# oplab_pth.net
KiCad netlist of a schematic drawn in EAGLE
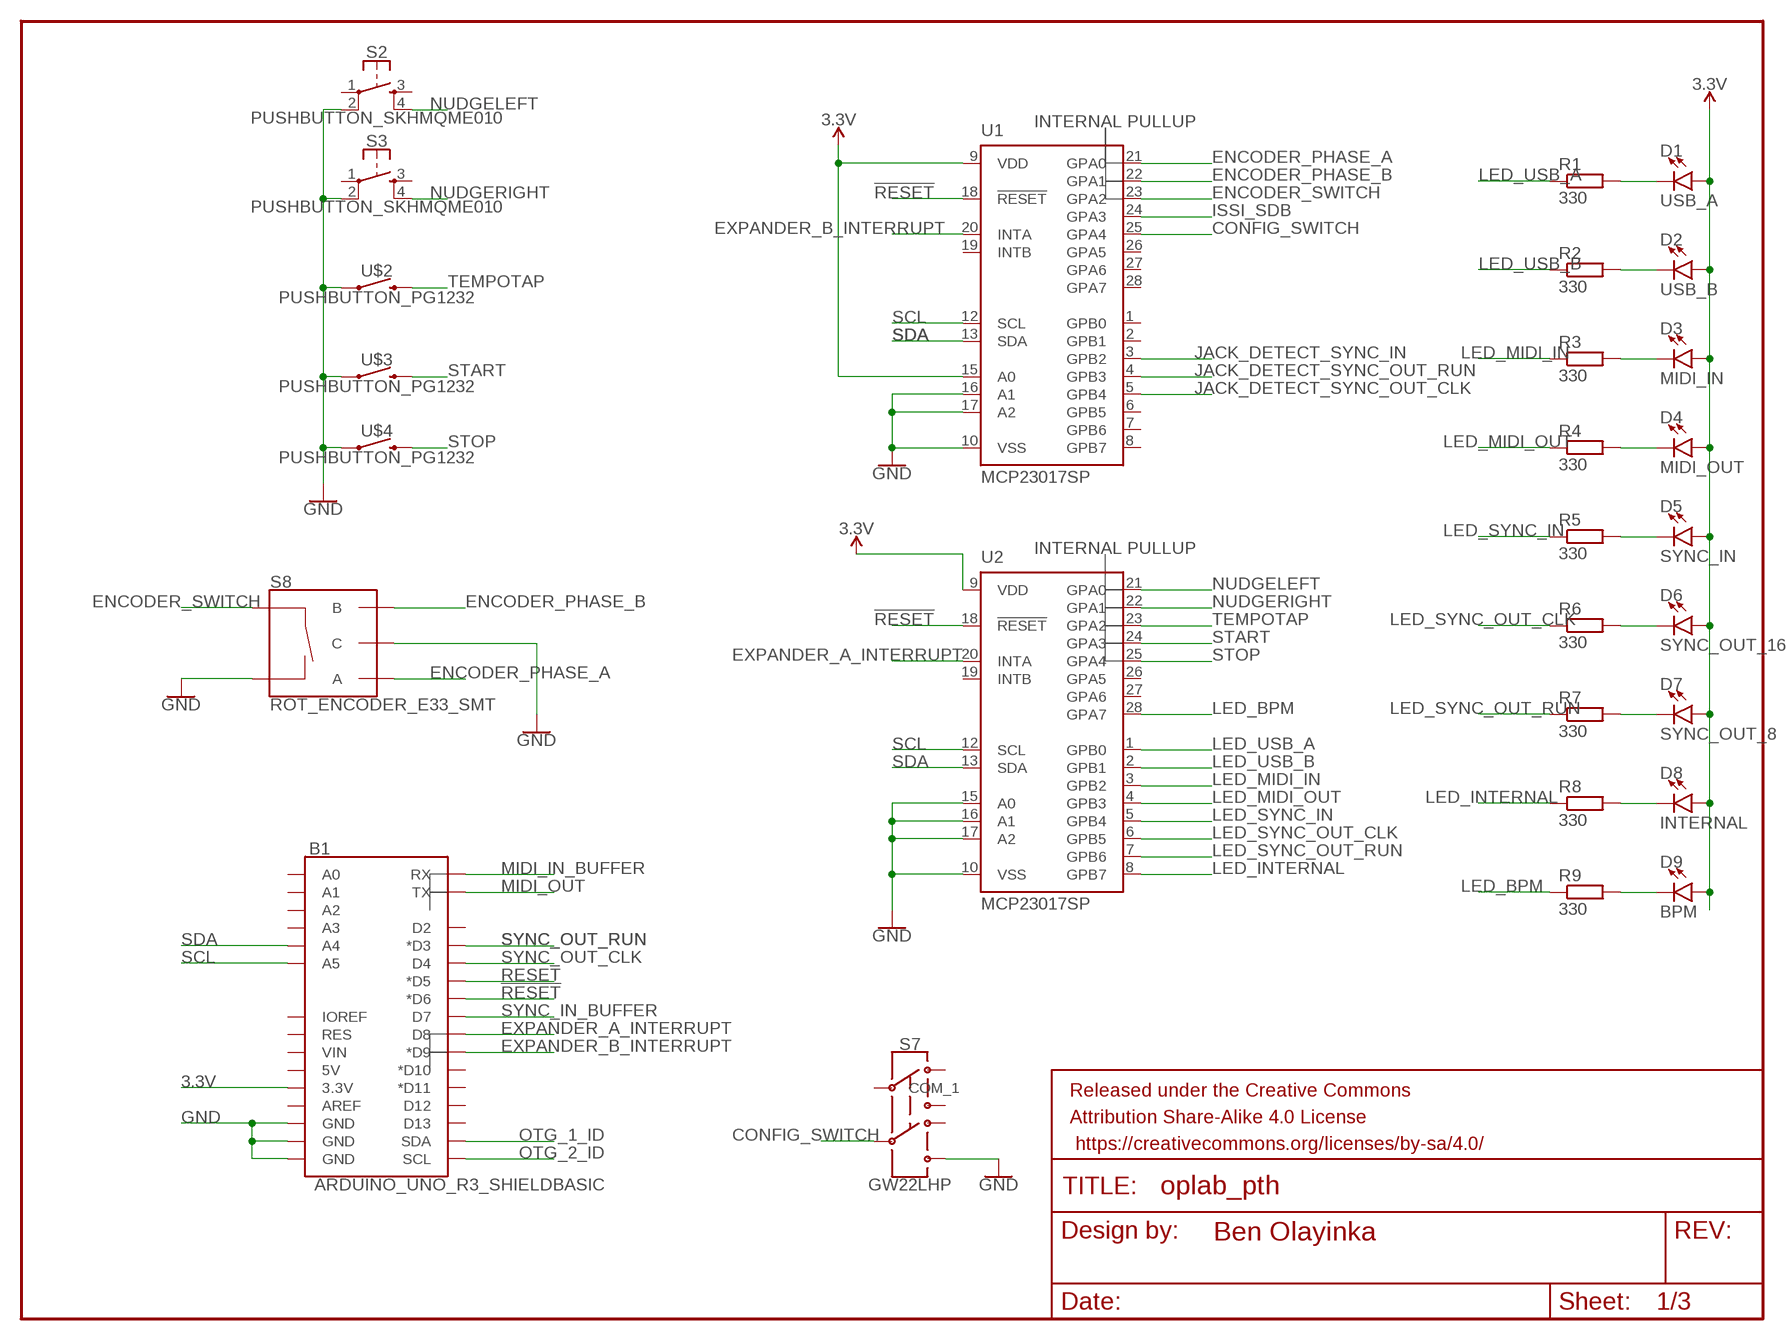
[diagram p0: schematic, sheet 1]
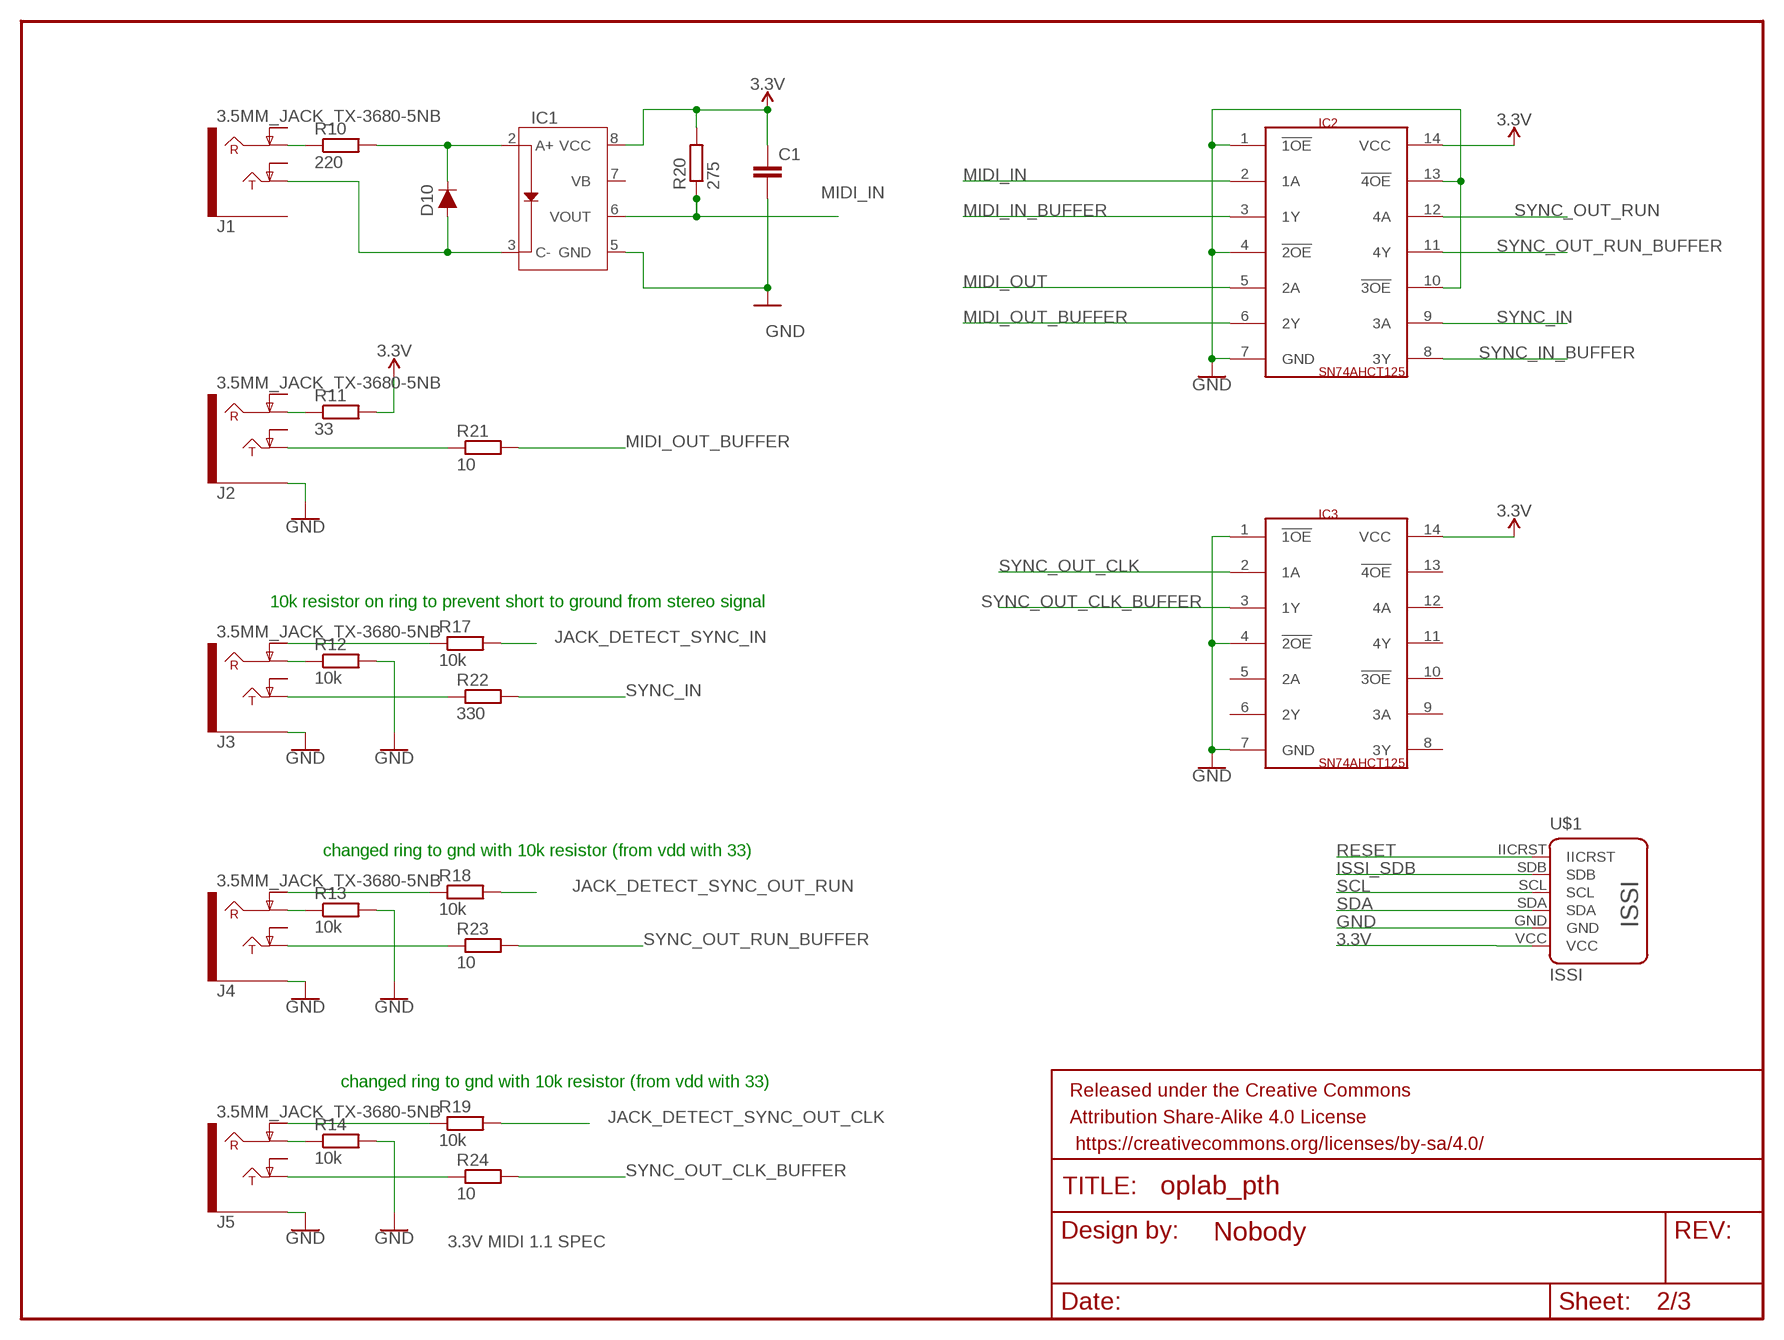
[diagram p1: schematic, sheet 2]
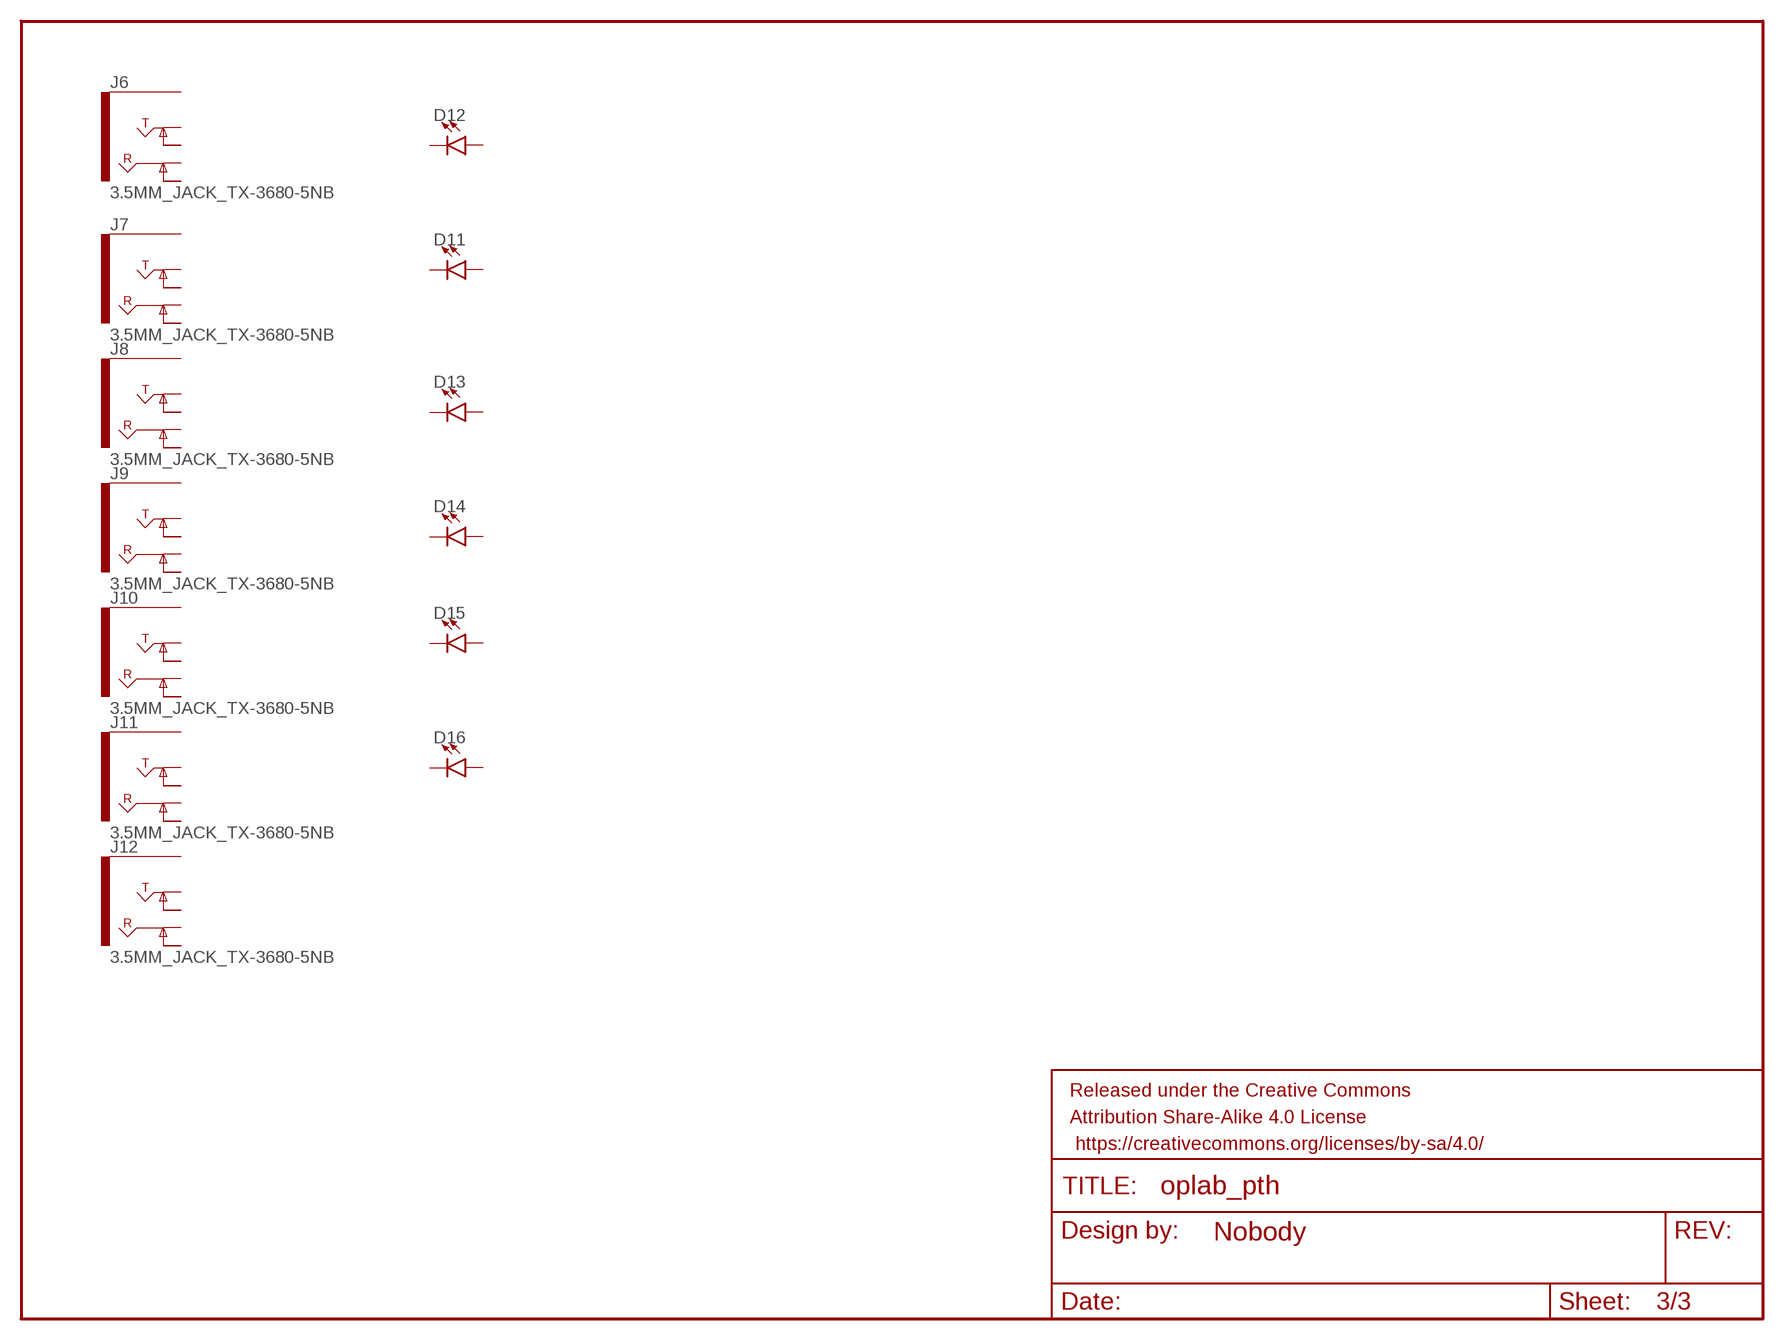
[diagram p2: schematic, sheet 3]

(export (version "E")
  (design (tool "Eeschema 10.0.6"))
  (components
    (comp (ref "C1")
      (value "C-EU025-024X044")
      (footprint "eagle-import:C025-024X044")
      (libsource (lib "eagle-import") (part "C-EU025-024X044"))
    )
    (comp (ref "D10")
      (value "200mA/100V/1V")
      (footprint "eagle-import:DIODE-1N4148")
      (libsource (lib "eagle-import") (part "DIODE-1N4148"))
    )
    (comp (ref "FRAME2")
      (value "FRAME-LETTERNO_PACKAGE")
      (footprint "eagle-import:DUMMY")
      (fields (field (name "DESIGNER") "Nobody"))
      (libsource (lib "eagle-import") (part "FRAME-LETTERNO_PACKAGE"))
    )
    (comp (ref "IC1")
      (value "OPTO_DARLINGTON_HCPL0701")
      (footprint "eagle-import:OPTO_DARLINGTON_SOIC127P594X363-8N")
      (fields
        (field (name "MANUFACTURER_PART_NUMBER") "HCPL0701")
        (field (name "MOUSER_PART_NUMBER") "512-HCPL0701")
        (field (name "RS_PART_NUMBER") "9034263P")
      )
      (libsource (lib "eagle-import") (part "OPTO_DARLINGTON_HCPL0701"))
    )
    (comp (ref "IC2")
      (value "SN74AHCT125")
      (footprint "eagle-import:SN74AHCT_DIP794W53P254L1930H508Q14N")
      (fields
        (field (name "MANUFACTURER_PART_NUMBER") "SN74HCT14N")
        (field (name "MOUSER_PART_NUMBER") "595-SN74HCT14N")
        (field (name "RS_PART_NUMBER") "0526331")
      )
      (libsource (lib "eagle-import") (part "SN74AHCT125"))
    )
    (comp (ref "IC3")
      (value "SN74AHCT125")
      (footprint "eagle-import:SN74AHCT_DIP794W53P254L1930H508Q14N")
      (fields
        (field (name "MANUFACTURER_PART_NUMBER") "SN74HCT14N")
        (field (name "MOUSER_PART_NUMBER") "595-SN74HCT14N")
        (field (name "RS_PART_NUMBER") "0526331")
      )
      (libsource (lib "eagle-import") (part "SN74AHCT125"))
    )
    (comp (ref "J1")
      (value "3.5MM_JACK_TX-3680-5NB")
      (footprint "eagle-import:3.5MM_JACK_TX36805NB")
      (libsource (lib "eagle-import") (part "3.5MM_JACK_TX-3680-5NB"))
    )
    (comp (ref "J2")
      (value "3.5MM_JACK_TX-3680-5NB")
      (footprint "eagle-import:3.5MM_JACK_TX36805NB")
      (libsource (lib "eagle-import") (part "3.5MM_JACK_TX-3680-5NB"))
    )
    (comp (ref "J3")
      (value "3.5MM_JACK_TX-3680-5NB")
      (footprint "eagle-import:3.5MM_JACK_TX36805NB")
      (libsource (lib "eagle-import") (part "3.5MM_JACK_TX-3680-5NB"))
    )
    (comp (ref "J4")
      (value "3.5MM_JACK_TX-3680-5NB")
      (footprint "eagle-import:3.5MM_JACK_TX36805NB")
      (libsource (lib "eagle-import") (part "3.5MM_JACK_TX-3680-5NB"))
    )
    (comp (ref "J5")
      (value "3.5MM_JACK_TX-3680-5NB")
      (footprint "eagle-import:3.5MM_JACK_TX36805NB")
      (libsource (lib "eagle-import") (part "3.5MM_JACK_TX-3680-5NB"))
    )
    (comp (ref "R10")
      (value "220")
      (footprint "eagle-import:0207_10")
      (libsource (lib "eagle-import") (part "R-EU_0207/10"))
    )
    (comp (ref "R11")
      (value "33")
      (footprint "eagle-import:0207_10")
      (libsource (lib "eagle-import") (part "R-EU_0207/10"))
    )
    (comp (ref "R12")
      (value "10k")
      (footprint "eagle-import:0207_10")
      (libsource (lib "eagle-import") (part "R-EU_0207/10"))
    )
    (comp (ref "R13")
      (value "10k")
      (footprint "eagle-import:0207_10")
      (libsource (lib "eagle-import") (part "R-EU_0207/10"))
    )
    (comp (ref "R14")
      (value "10k")
      (footprint "eagle-import:0207_10")
      (libsource (lib "eagle-import") (part "R-EU_0207/10"))
    )
    (comp (ref "R17")
      (value "10k")
      (footprint "eagle-import:0207_10")
      (libsource (lib "eagle-import") (part "R-EU_0207/10"))
    )
    (comp (ref "R18")
      (value "10k")
      (footprint "eagle-import:0207_10")
      (libsource (lib "eagle-import") (part "R-EU_0207/10"))
    )
    (comp (ref "R19")
      (value "10k")
      (footprint "eagle-import:0207_10")
      (libsource (lib "eagle-import") (part "R-EU_0207/10"))
    )
    (comp (ref "R20")
      (value "275")
      (footprint "eagle-import:0207_10")
      (libsource (lib "eagle-import") (part "R-EU_0207/10"))
    )
    (comp (ref "R21")
      (value "10")
      (footprint "eagle-import:0207_10")
      (libsource (lib "eagle-import") (part "R-EU_0207/10"))
    )
    (comp (ref "R22")
      (value "330")
      (footprint "eagle-import:0207_10")
      (libsource (lib "eagle-import") (part "R-EU_0207/10"))
    )
    (comp (ref "R23")
      (value "10")
      (footprint "eagle-import:0207_10")
      (libsource (lib "eagle-import") (part "R-EU_0207/10"))
    )
    (comp (ref "R24")
      (value "10")
      (footprint "eagle-import:0207_10")
      (libsource (lib "eagle-import") (part "R-EU_0207/10"))
    )
    (comp (ref "U$1")
      (value "ISSI")
      (footprint "eagle-import:ISSI")
      (libsource (lib "eagle-import") (part "ISSI"))
    )
    (comp (ref "D11")
      (value "LED5MM")
      (footprint "eagle-import:LED_5MM")
      (libsource (lib "eagle-import") (part "LED5MM"))
    )
    (comp (ref "D12")
      (value "LED5MM")
      (footprint "eagle-import:LED_5MM")
      (libsource (lib "eagle-import") (part "LED5MM"))
    )
    (comp (ref "D13")
      (value "LED5MM")
      (footprint "eagle-import:LED_5MM")
      (libsource (lib "eagle-import") (part "LED5MM"))
    )
    (comp (ref "D14")
      (value "LED5MM")
      (footprint "eagle-import:LED_5MM")
      (libsource (lib "eagle-import") (part "LED5MM"))
    )
    (comp (ref "D15")
      (value "LED5MM")
      (footprint "eagle-import:LED_5MM")
      (libsource (lib "eagle-import") (part "LED5MM"))
    )
    (comp (ref "D16")
      (value "LED5MM")
      (footprint "eagle-import:LED_5MM")
      (libsource (lib "eagle-import") (part "LED5MM"))
    )
    (comp (ref "FRAME3")
      (value "FRAME-LETTERNO_PACKAGE")
      (footprint "eagle-import:DUMMY")
      (fields (field (name "DESIGNER") "Nobody"))
      (libsource (lib "eagle-import") (part "FRAME-LETTERNO_PACKAGE"))
    )
    (comp (ref "J6")
      (value "3.5MM_JACK_TX-3680-5NB")
      (footprint "eagle-import:3.5MM_JACK_TX36805NB")
      (libsource (lib "eagle-import") (part "3.5MM_JACK_TX-3680-5NB"))
    )
    (comp (ref "J7")
      (value "3.5MM_JACK_TX-3680-5NB")
      (footprint "eagle-import:3.5MM_JACK_TX36805NB")
      (libsource (lib "eagle-import") (part "3.5MM_JACK_TX-3680-5NB"))
    )
    (comp (ref "J8")
      (value "3.5MM_JACK_TX-3680-5NB")
      (footprint "eagle-import:3.5MM_JACK_TX36805NB")
      (libsource (lib "eagle-import") (part "3.5MM_JACK_TX-3680-5NB"))
    )
    (comp (ref "J9")
      (value "3.5MM_JACK_TX-3680-5NB")
      (footprint "eagle-import:3.5MM_JACK_TX36805NB")
      (libsource (lib "eagle-import") (part "3.5MM_JACK_TX-3680-5NB"))
    )
    (comp (ref "J10")
      (value "3.5MM_JACK_TX-3680-5NB")
      (footprint "eagle-import:3.5MM_JACK_TX36805NB")
      (libsource (lib "eagle-import") (part "3.5MM_JACK_TX-3680-5NB"))
    )
    (comp (ref "J11")
      (value "3.5MM_JACK_TX-3680-5NB")
      (footprint "eagle-import:3.5MM_JACK_TX36805NB")
      (libsource (lib "eagle-import") (part "3.5MM_JACK_TX-3680-5NB"))
    )
    (comp (ref "J12")
      (value "3.5MM_JACK_TX-3680-5NB")
      (footprint "eagle-import:3.5MM_JACK_TX36805NB")
      (libsource (lib "eagle-import") (part "3.5MM_JACK_TX-3680-5NB"))
    )
    (comp (ref "B1")
      (value "ARDUINO_UNO_R3_SHIELDBASIC")
      (footprint "eagle-import:UNO_R3_SHIELD")
      (libsource (lib "eagle-import") (part "ARDUINO_UNO_R3_SHIELDBASIC"))
    )
    (comp (ref "D1")
      (value "USB_A")
      (footprint "eagle-import:LED_5MM")
      (libsource (lib "eagle-import") (part "LED5MM"))
    )
    (comp (ref "D2")
      (value "USB_B")
      (footprint "eagle-import:LED_5MM")
      (libsource (lib "eagle-import") (part "LED5MM"))
    )
    (comp (ref "D3")
      (value "MIDI_IN")
      (footprint "eagle-import:LED_5MM")
      (libsource (lib "eagle-import") (part "LED5MM"))
    )
    (comp (ref "D4")
      (value "MIDI_OUT")
      (footprint "eagle-import:LED_5MM")
      (libsource (lib "eagle-import") (part "LED5MM"))
    )
    (comp (ref "D5")
      (value "SYNC_IN")
      (footprint "eagle-import:LED_5MM")
      (libsource (lib "eagle-import") (part "LED5MM"))
    )
    (comp (ref "D6")
      (value "SYNC_OUT_16")
      (footprint "eagle-import:LED_5MM")
      (libsource (lib "eagle-import") (part "LED5MM"))
    )
    (comp (ref "D7")
      (value "SYNC_OUT_8")
      (footprint "eagle-import:LED_5MM")
      (libsource (lib "eagle-import") (part "LED5MM"))
    )
    (comp (ref "D8")
      (value "INTERNAL")
      (footprint "eagle-import:LED_5MM")
      (libsource (lib "eagle-import") (part "LED5MM"))
    )
    (comp (ref "D9")
      (value "BPM")
      (footprint "eagle-import:LED_5MM")
      (libsource (lib "eagle-import") (part "LED5MM"))
    )
    (comp (ref "FRAME1")
      (value "FRAME-LETTERNO_PACKAGE")
      (footprint "eagle-import:DUMMY")
      (fields (field (name "DESIGNER") "Nobody") (field (name "DESIGNER_1") "Ben Olayinka"))
      (libsource (lib "eagle-import") (part "FRAME-LETTERNO_PACKAGE"))
    )
    (comp (ref "R1")
      (value "330")
      (footprint "eagle-import:0207_10")
      (libsource (lib "eagle-import") (part "R-EU_0207/10"))
    )
    (comp (ref "R2")
      (value "330")
      (footprint "eagle-import:0207_10")
      (libsource (lib "eagle-import") (part "R-EU_0207/10"))
    )
    (comp (ref "R3")
      (value "330")
      (footprint "eagle-import:0207_10")
      (libsource (lib "eagle-import") (part "R-EU_0207/10"))
    )
    (comp (ref "R4")
      (value "330")
      (footprint "eagle-import:0207_10")
      (libsource (lib "eagle-import") (part "R-EU_0207/10"))
    )
    (comp (ref "R5")
      (value "330")
      (footprint "eagle-import:0207_10")
      (libsource (lib "eagle-import") (part "R-EU_0207/10"))
    )
    (comp (ref "R6")
      (value "330")
      (footprint "eagle-import:0207_10")
      (libsource (lib "eagle-import") (part "R-EU_0207/10"))
    )
    (comp (ref "R7")
      (value "330")
      (footprint "eagle-import:0207_10")
      (libsource (lib "eagle-import") (part "R-EU_0207/10"))
    )
    (comp (ref "R8")
      (value "330")
      (footprint "eagle-import:0207_10")
      (libsource (lib "eagle-import") (part "R-EU_0207/10"))
    )
    (comp (ref "R9")
      (value "330")
      (footprint "eagle-import:0207_10")
      (libsource (lib "eagle-import") (part "R-EU_0207/10"))
    )
    (comp (ref "S2")
      (value "PUSHBUTTON_SKHMQME010")
      (footprint "eagle-import:PUSHUTTON_SKHMQLE010")
      (libsource (lib "eagle-import") (part "PUSHBUTTON_SKHMQME010"))
    )
    (comp (ref "S3")
      (value "PUSHBUTTON_SKHMQME010")
      (footprint "eagle-import:PUSHUTTON_SKHMQLE010")
      (libsource (lib "eagle-import") (part "PUSHBUTTON_SKHMQME010"))
    )
    (comp (ref "S7")
      (value "GW22LHP")
      (footprint "eagle-import:GW22LHP")
      (fields (field (name "MOUSER_PART_NUMBER") "633-GW22LHP"))
      (libsource (lib "eagle-import") (part "GW22LHP"))
    )
    (comp (ref "S8")
      (value "ROT_ENCODER_E33_SMT")
      (footprint "eagle-import:ROT_ENCODER_E33_SMT")
      (libsource (lib "eagle-import") (part "ROT_ENCODER_E33_SMT"))
    )
    (comp (ref "U$2")
      (value "PUSHBUTTON_PG1232")
      (footprint "eagle-import:PUSHBUTTON_PG1232")
      (libsource (lib "eagle-import") (part "PUSHBUTTON_PG1232"))
    )
    (comp (ref "U$3")
      (value "PUSHBUTTON_PG1232")
      (footprint "eagle-import:PUSHBUTTON_PG1232")
      (libsource (lib "eagle-import") (part "PUSHBUTTON_PG1232"))
    )
    (comp (ref "U$4")
      (value "PUSHBUTTON_PG1232")
      (footprint "eagle-import:PUSHBUTTON_PG1232")
      (libsource (lib "eagle-import") (part "PUSHBUTTON_PG1232"))
    )
    (comp (ref "U1")
      (value "MCP23017SP")
      (footprint "eagle-import:DIL28-3")
      (libsource (lib "eagle-import") (part "MCP23017SP"))
    )
    (comp (ref "U2")
      (value "MCP23017SP")
      (footprint "eagle-import:DIL28-3")
      (libsource (lib "eagle-import") (part "MCP23017SP"))
    )
  )
  (nets
    (net (code "1") (name "3.3V") (class "Default")
      (node (ref "B1") (pin "3.3V") (pinfunction "3.3V_3.3V") (pintype "bidirectional"))
      (node (ref "C1") (pin "1") (pinfunction "1_1") (pintype "passive"))
      (node (ref "D1") (pin "A") (pinfunction "A_A") (pintype "passive"))
      (node (ref "D2") (pin "A") (pinfunction "A_A") (pintype "passive"))
      (node (ref "D3") (pin "A") (pinfunction "A_A") (pintype "passive"))
      (node (ref "D4") (pin "A") (pinfunction "A_A") (pintype "passive"))
      (node (ref "D5") (pin "A") (pinfunction "A_A") (pintype "passive"))
      (node (ref "D6") (pin "A") (pinfunction "A_A") (pintype "passive"))
      (node (ref "D7") (pin "A") (pinfunction "A_A") (pintype "passive"))
      (node (ref "D8") (pin "A") (pinfunction "A_A") (pintype "passive"))
      (node (ref "D9") (pin "A") (pinfunction "A_A") (pintype "passive"))
      (node (ref "IC1") (pin "8") (pinfunction "VCC_8") (pintype "bidirectional"))
      (node (ref "IC2") (pin "14") (pinfunction "VCC_14") (pintype "input"))
      (node (ref "IC3") (pin "14") (pinfunction "VCC_14") (pintype "input"))
      (node (ref "R11") (pin "2") (pinfunction "2_2") (pintype "passive"))
      (node (ref "R20") (pin "2") (pinfunction "2_2") (pintype "passive"))
      (node (ref "U$1") (pin "VCC") (pinfunction "VCC_VCC") (pintype "passive"))
      (node (ref "U1") (pin "15") (pinfunction "A0_15") (pintype "input"))
      (node (ref "U1") (pin "9") (pinfunction "VDD_9") (pintype "power_in"))
      (node (ref "U2") (pin "9") (pinfunction "VDD_9") (pintype "power_in"))
    )
    (net (code "2") (name "CONFIG_SWITCH") (class "Default")
      (node (ref "S7") (pin "5") (pinfunction "COM_2_5") (pintype "bidirectional"))
      (node (ref "U1") (pin "25") (pinfunction "GPA4_25") (pintype "bidirectional"))
    )
    (net (code "3") (name "ENCODER_PHASE_A") (class "Default")
      (node (ref "S8") (pin "A") (pinfunction "A_A") (pintype "bidirectional"))
      (node (ref "U1") (pin "21") (pinfunction "GPA0_21") (pintype "bidirectional"))
    )
    (net (code "4") (name "ENCODER_PHASE_B") (class "Default")
      (node (ref "S8") (pin "B") (pinfunction "B_B") (pintype "bidirectional"))
      (node (ref "U1") (pin "22") (pinfunction "GPA1_22") (pintype "bidirectional"))
    )
    (net (code "5") (name "ENCODER_SWITCH") (class "Default")
      (node (ref "S8") (pin "S1") (pinfunction "SW+_S1") (pintype "bidirectional"))
      (node (ref "U1") (pin "23") (pinfunction "GPA2_23") (pintype "bidirectional"))
    )
    (net (code "6") (name "EXPANDER_A_INTERRUPT") (class "Default")
      (node (ref "B1") (pin "D8") (pinfunction "D8_D8") (pintype "bidirectional"))
      (node (ref "U2") (pin "20") (pinfunction "INTA_20") (pintype "output"))
    )
    (net (code "7") (name "EXPANDER_B_INTERRUPT") (class "Default")
      (node (ref "B1") (pin "D9") (pinfunction "*D9_D9") (pintype "bidirectional"))
      (node (ref "U1") (pin "20") (pinfunction "INTA_20") (pintype "output"))
    )
    (net (code "8") (name "GND") (class "Default")
      (node (ref "B1") (pin "GND@0") (pinfunction "GND_GND@0") (pintype "bidirectional"))
      (node (ref "B1") (pin "GND@1") (pinfunction "GND_GND@1") (pintype "bidirectional"))
      (node (ref "B1") (pin "GND@2") (pinfunction "GND_GND@2") (pintype "bidirectional"))
      (node (ref "C1") (pin "2") (pinfunction "2_2") (pintype "passive"))
      (node (ref "IC1") (pin "5") (pinfunction "GND_5") (pintype "bidirectional"))
      (node (ref "IC2") (pin "1") (pinfunction "~{1OE}_1") (pintype "input"))
      (node (ref "IC2") (pin "10") (pinfunction "~{3OE}_10") (pintype "input"))
      (node (ref "IC2") (pin "13") (pinfunction "~{4OE}_13") (pintype "input"))
      (node (ref "IC2") (pin "4") (pinfunction "~{2OE}_4") (pintype "input"))
      (node (ref "IC2") (pin "7") (pinfunction "GND_7") (pintype "input"))
      (node (ref "IC3") (pin "1") (pinfunction "~{1OE}_1") (pintype "input"))
      (node (ref "IC3") (pin "4") (pinfunction "~{2OE}_4") (pintype "input"))
      (node (ref "IC3") (pin "7") (pinfunction "GND_7") (pintype "input"))
      (node (ref "J2") (pin "1.EARTH") (pinfunction "EARTH_1.EARTH") (pintype "bidirectional"))
      (node (ref "J3") (pin "1.EARTH") (pinfunction "EARTH_1.EARTH") (pintype "bidirectional"))
      (node (ref "J4") (pin "1.EARTH") (pinfunction "EARTH_1.EARTH") (pintype "bidirectional"))
      (node (ref "J5") (pin "1.EARTH") (pinfunction "EARTH_1.EARTH") (pintype "bidirectional"))
      (node (ref "R12") (pin "2") (pinfunction "2_2") (pintype "passive"))
      (node (ref "R13") (pin "2") (pinfunction "2_2") (pintype "passive"))
      (node (ref "R14") (pin "2") (pinfunction "2_2") (pintype "passive"))
      (node (ref "S2") (pin "2") (pinfunction "2_2") (pintype "passive"))
      (node (ref "S3") (pin "2") (pinfunction "2_2") (pintype "passive"))
      (node (ref "S7") (pin "4") (pinfunction "NO_2_4") (pintype "bidirectional"))
      (node (ref "S8") (pin "C") (pinfunction "C_C") (pintype "bidirectional"))
      (node (ref "S8") (pin "S2") (pinfunction "SW-_S2") (pintype "bidirectional"))
      (node (ref "U$1") (pin "GND") (pinfunction "GND_GND") (pintype "passive"))
      (node (ref "U$2") (pin "1") (pinfunction "1_1") (pintype "passive"))
      (node (ref "U$3") (pin "1") (pinfunction "1_1") (pintype "passive"))
      (node (ref "U$4") (pin "1") (pinfunction "1_1") (pintype "passive"))
      (node (ref "U1") (pin "10") (pinfunction "VSS_10") (pintype "power_in"))
      (node (ref "U1") (pin "16") (pinfunction "A1_16") (pintype "input"))
      (node (ref "U1") (pin "17") (pinfunction "A2_17") (pintype "input"))
      (node (ref "U2") (pin "10") (pinfunction "VSS_10") (pintype "power_in"))
      (node (ref "U2") (pin "15") (pinfunction "A0_15") (pintype "input"))
      (node (ref "U2") (pin "16") (pinfunction "A1_16") (pintype "input"))
      (node (ref "U2") (pin "17") (pinfunction "A2_17") (pintype "input"))
    )
    (net (code "9") (name "ISSI_SDB") (class "Default")
      (node (ref "U$1") (pin "SDB") (pinfunction "SDB_SDB") (pintype "passive"))
      (node (ref "U1") (pin "24") (pinfunction "GPA3_24") (pintype "bidirectional"))
    )
    (net (code "10") (name "JACK_DETECT_SYNC_IN") (class "Default")
      (node (ref "R17") (pin "2") (pinfunction "2_2") (pintype "passive"))
      (node (ref "U1") (pin "3") (pinfunction "GPB2_3") (pintype "bidirectional"))
    )
    (net (code "11") (name "JACK_DETECT_SYNC_OUT_CLK") (class "Default")
      (node (ref "R19") (pin "2") (pinfunction "2_2") (pintype "passive"))
      (node (ref "U1") (pin "5") (pinfunction "GPB4_5") (pintype "bidirectional"))
    )
    (net (code "12") (name "JACK_DETECT_SYNC_OUT_RUN") (class "Default")
      (node (ref "R18") (pin "2") (pinfunction "2_2") (pintype "passive"))
      (node (ref "U1") (pin "4") (pinfunction "GPB3_4") (pintype "bidirectional"))
    )
    (net (code "13") (name "LED_BPM") (class "Default")
      (node (ref "R9") (pin "1") (pinfunction "1_1") (pintype "passive"))
      (node (ref "U2") (pin "28") (pinfunction "GPA7_28") (pintype "bidirectional"))
    )
    (net (code "14") (name "LED_INTERNAL") (class "Default")
      (node (ref "R8") (pin "1") (pinfunction "1_1") (pintype "passive"))
      (node (ref "U2") (pin "8") (pinfunction "GPB7_8") (pintype "bidirectional"))
    )
    (net (code "15") (name "LED_MIDI_IN") (class "Default")
      (node (ref "R3") (pin "1") (pinfunction "1_1") (pintype "passive"))
      (node (ref "U2") (pin "3") (pinfunction "GPB2_3") (pintype "bidirectional"))
    )
    (net (code "16") (name "LED_MIDI_OUT") (class "Default")
      (node (ref "R4") (pin "1") (pinfunction "1_1") (pintype "passive"))
      (node (ref "U2") (pin "4") (pinfunction "GPB3_4") (pintype "bidirectional"))
    )
    (net (code "17") (name "LED_SYNC_IN") (class "Default")
      (node (ref "R5") (pin "1") (pinfunction "1_1") (pintype "passive"))
      (node (ref "U2") (pin "5") (pinfunction "GPB4_5") (pintype "bidirectional"))
    )
    (net (code "18") (name "LED_SYNC_OUT_CLK") (class "Default")
      (node (ref "R6") (pin "1") (pinfunction "1_1") (pintype "passive"))
      (node (ref "U2") (pin "6") (pinfunction "GPB5_6") (pintype "bidirectional"))
    )
    (net (code "19") (name "LED_SYNC_OUT_RUN") (class "Default")
      (node (ref "R7") (pin "1") (pinfunction "1_1") (pintype "passive"))
      (node (ref "U2") (pin "7") (pinfunction "GPB6_7") (pintype "bidirectional"))
    )
    (net (code "20") (name "LED_USB_A") (class "Default")
      (node (ref "R1") (pin "1") (pinfunction "1_1") (pintype "passive"))
      (node (ref "U2") (pin "1") (pinfunction "GPB0_1") (pintype "bidirectional"))
    )
    (net (code "21") (name "LED_USB_B") (class "Default")
      (node (ref "R2") (pin "1") (pinfunction "1_1") (pintype "passive"))
      (node (ref "U2") (pin "2") (pinfunction "GPB1_2") (pintype "bidirectional"))
    )
    (net (code "22") (name "MIDI_IN") (class "Default")
      (node (ref "IC1") (pin "6") (pinfunction "VOUT_6") (pintype "bidirectional"))
      (node (ref "IC2") (pin "2") (pinfunction "1A_2") (pintype "input"))
      (node (ref "R20") (pin "1") (pinfunction "1_1") (pintype "passive"))
    )
    (net (code "23") (name "MIDI_IN_BUFFER") (class "Default")
      (node (ref "B1") (pin "RX") (pinfunction "RX_RX") (pintype "bidirectional"))
      (node (ref "IC2") (pin "3") (pinfunction "1Y_3") (pintype "output"))
    )
    (net (code "24") (name "MIDI_OUT") (class "Default")
      (node (ref "B1") (pin "TX") (pinfunction "TX_TX") (pintype "bidirectional"))
      (node (ref "IC2") (pin "5") (pinfunction "2A_5") (pintype "input"))
    )
    (net (code "25") (name "MIDI_OUT_BUFFER") (class "Default")
      (node (ref "IC2") (pin "6") (pinfunction "2Y_6") (pintype "output"))
      (node (ref "R21") (pin "2") (pinfunction "2_2") (pintype "passive"))
    )
    (net (code "26") (name "NUDGELEFT") (class "Default")
      (node (ref "S2") (pin "4") (pinfunction "4_4") (pintype "passive"))
      (node (ref "U2") (pin "21") (pinfunction "GPA0_21") (pintype "bidirectional"))
    )
    (net (code "27") (name "NUDGERIGHT") (class "Default")
      (node (ref "S3") (pin "4") (pinfunction "4_4") (pintype "passive"))
      (node (ref "U2") (pin "22") (pinfunction "GPA1_22") (pintype "bidirectional"))
    )
    (net (code "28") (name "Net-(D1-C)") (class "Default")
      (node (ref "D1") (pin "K") (pinfunction "C_K") (pintype "passive"))
      (node (ref "R1") (pin "2") (pinfunction "2_2") (pintype "passive"))
    )
    (net (code "29") (name "Net-(D2-C)") (class "Default")
      (node (ref "D2") (pin "K") (pinfunction "C_K") (pintype "passive"))
      (node (ref "R2") (pin "2") (pinfunction "2_2") (pintype "passive"))
    )
    (net (code "30") (name "Net-(D3-C)") (class "Default")
      (node (ref "D3") (pin "K") (pinfunction "C_K") (pintype "passive"))
      (node (ref "R3") (pin "2") (pinfunction "2_2") (pintype "passive"))
    )
    (net (code "31") (name "Net-(D4-C)") (class "Default")
      (node (ref "D4") (pin "K") (pinfunction "C_K") (pintype "passive"))
      (node (ref "R4") (pin "2") (pinfunction "2_2") (pintype "passive"))
    )
    (net (code "32") (name "Net-(D5-C)") (class "Default")
      (node (ref "D5") (pin "K") (pinfunction "C_K") (pintype "passive"))
      (node (ref "R5") (pin "2") (pinfunction "2_2") (pintype "passive"))
    )
    (net (code "33") (name "Net-(D6-C)") (class "Default")
      (node (ref "D6") (pin "K") (pinfunction "C_K") (pintype "passive"))
      (node (ref "R6") (pin "2") (pinfunction "2_2") (pintype "passive"))
    )
    (net (code "34") (name "Net-(D7-C)") (class "Default")
      (node (ref "D7") (pin "K") (pinfunction "C_K") (pintype "passive"))
      (node (ref "R7") (pin "2") (pinfunction "2_2") (pintype "passive"))
    )
    (net (code "35") (name "Net-(D8-C)") (class "Default")
      (node (ref "D8") (pin "K") (pinfunction "C_K") (pintype "passive"))
      (node (ref "R8") (pin "2") (pinfunction "2_2") (pintype "passive"))
    )
    (net (code "36") (name "Net-(D9-C)") (class "Default")
      (node (ref "D9") (pin "K") (pinfunction "C_K") (pintype "passive"))
      (node (ref "R9") (pin "2") (pinfunction "2_2") (pintype "passive"))
    )
    (net (code "37") (name "Net-(IC1-A+)") (class "Default")
      (node (ref "D10") (pin "C") (pinfunction "C_C") (pintype "passive"))
      (node (ref "IC1") (pin "2") (pinfunction "A+_2") (pintype "bidirectional"))
      (node (ref "R10") (pin "2") (pinfunction "2_2") (pintype "passive"))
    )
    (net (code "38") (name "Net-(IC1-C-)") (class "Default")
      (node (ref "D10") (pin "A") (pinfunction "A_A") (pintype "passive"))
      (node (ref "IC1") (pin "3") (pinfunction "C-_3") (pintype "bidirectional"))
      (node (ref "J1") (pin "2.TIP") (pinfunction "TIP_2.TIP") (pintype "bidirectional"))
    )
    (net (code "39") (name "Net-(J1-RING)") (class "Default")
      (node (ref "J1") (pin "3.RING") (pinfunction "RING_3.RING") (pintype "bidirectional"))
      (node (ref "R10") (pin "1") (pinfunction "1_1") (pintype "passive"))
    )
    (net (code "40") (name "Net-(J2-RING)") (class "Default")
      (node (ref "J2") (pin "3.RING") (pinfunction "RING_3.RING") (pintype "bidirectional"))
      (node (ref "R11") (pin "1") (pinfunction "1_1") (pintype "passive"))
    )
    (net (code "41") (name "Net-(J2-TIP)") (class "Default")
      (node (ref "J2") (pin "2.TIP") (pinfunction "TIP_2.TIP") (pintype "bidirectional"))
      (node (ref "R21") (pin "1") (pinfunction "1_1") (pintype "passive"))
    )
    (net (code "42") (name "Net-(J3-RING)") (class "Default")
      (node (ref "J3") (pin "3.RING") (pinfunction "RING_3.RING") (pintype "bidirectional"))
      (node (ref "R12") (pin "1") (pinfunction "1_1") (pintype "passive"))
    )
    (net (code "43") (name "Net-(J3-RING-NORM)") (class "Default")
      (node (ref "J3") (pin "5.RINGNORM") (pinfunction "RING-NORM_5.RINGNORM") (pintype "bidirectional"))
      (node (ref "R17") (pin "1") (pinfunction "1_1") (pintype "passive"))
    )
    (net (code "44") (name "Net-(J3-TIP)") (class "Default")
      (node (ref "J3") (pin "2.TIP") (pinfunction "TIP_2.TIP") (pintype "bidirectional"))
      (node (ref "R22") (pin "1") (pinfunction "1_1") (pintype "passive"))
    )
    (net (code "45") (name "Net-(J4-RING)") (class "Default")
      (node (ref "J4") (pin "3.RING") (pinfunction "RING_3.RING") (pintype "bidirectional"))
      (node (ref "R13") (pin "1") (pinfunction "1_1") (pintype "passive"))
    )
    (net (code "46") (name "Net-(J4-RING-NORM)") (class "Default")
      (node (ref "J4") (pin "5.RINGNORM") (pinfunction "RING-NORM_5.RINGNORM") (pintype "bidirectional"))
      (node (ref "R18") (pin "1") (pinfunction "1_1") (pintype "passive"))
    )
    (net (code "47") (name "Net-(J4-TIP)") (class "Default")
      (node (ref "J4") (pin "2.TIP") (pinfunction "TIP_2.TIP") (pintype "bidirectional"))
      (node (ref "R23") (pin "1") (pinfunction "1_1") (pintype "passive"))
    )
    (net (code "48") (name "Net-(J5-RING)") (class "Default")
      (node (ref "J5") (pin "3.RING") (pinfunction "RING_3.RING") (pintype "bidirectional"))
      (node (ref "R14") (pin "1") (pinfunction "1_1") (pintype "passive"))
    )
    (net (code "49") (name "Net-(J5-RING-NORM)") (class "Default")
      (node (ref "J5") (pin "5.RINGNORM") (pinfunction "RING-NORM_5.RINGNORM") (pintype "bidirectional"))
      (node (ref "R19") (pin "1") (pinfunction "1_1") (pintype "passive"))
    )
    (net (code "50") (name "Net-(J5-TIP)") (class "Default")
      (node (ref "J5") (pin "2.TIP") (pinfunction "TIP_2.TIP") (pintype "bidirectional"))
      (node (ref "R24") (pin "1") (pinfunction "1_1") (pintype "passive"))
    )
    (net (code "51") (name "OTG_1_ID") (class "Default")
      (node (ref "B1") (pin "SDA") (pinfunction "SDA_SDA") (pintype "bidirectional"))
    )
    (net (code "52") (name "OTG_2_ID") (class "Default")
      (node (ref "B1") (pin "SCL") (pinfunction "SCL_SCL") (pintype "bidirectional"))
    )
    (net (code "53") (name "RESET") (class "Default")
      (node (ref "B1") (pin "D5") (pinfunction "*D5_D5") (pintype "bidirectional"))
      (node (ref "U$1") (pin "IICRST") (pinfunction "IICRST_IICRST") (pintype "passive"))
    )
    (net (code "54") (name "SCL") (class "Default")
      (node (ref "B1") (pin "A5") (pinfunction "A5_A5") (pintype "bidirectional"))
      (node (ref "U$1") (pin "SCL") (pinfunction "SCL_SCL") (pintype "passive"))
      (node (ref "U1") (pin "12") (pinfunction "SCL_12") (pintype "input"))
      (node (ref "U2") (pin "12") (pinfunction "SCL_12") (pintype "input"))
    )
    (net (code "55") (name "SDA") (class "Default")
      (node (ref "B1") (pin "A4") (pinfunction "A4_A4") (pintype "bidirectional"))
      (node (ref "U$1") (pin "SDA") (pinfunction "SDA_SDA") (pintype "passive"))
      (node (ref "U1") (pin "13") (pinfunction "SDA_13") (pintype "bidirectional"))
      (node (ref "U2") (pin "13") (pinfunction "SDA_13") (pintype "bidirectional"))
    )
    (net (code "56") (name "START") (class "Default")
      (node (ref "U$3") (pin "2") (pinfunction "2_2") (pintype "passive"))
      (node (ref "U2") (pin "24") (pinfunction "GPA3_24") (pintype "bidirectional"))
    )
    (net (code "57") (name "STOP") (class "Default")
      (node (ref "U$4") (pin "2") (pinfunction "2_2") (pintype "passive"))
      (node (ref "U2") (pin "25") (pinfunction "GPA4_25") (pintype "bidirectional"))
    )
    (net (code "58") (name "SYNC_IN") (class "Default")
      (node (ref "IC2") (pin "9") (pinfunction "3A_9") (pintype "input"))
      (node (ref "R22") (pin "2") (pinfunction "2_2") (pintype "passive"))
    )
    (net (code "59") (name "SYNC_IN_BUFFER") (class "Default")
      (node (ref "B1") (pin "D7") (pinfunction "D7_D7") (pintype "bidirectional"))
      (node (ref "IC2") (pin "8") (pinfunction "3Y_8") (pintype "output"))
    )
    (net (code "60") (name "SYNC_OUT_CLK") (class "Default")
      (node (ref "B1") (pin "D4") (pinfunction "D4_D4") (pintype "bidirectional"))
      (node (ref "IC3") (pin "2") (pinfunction "1A_2") (pintype "input"))
    )
    (net (code "61") (name "SYNC_OUT_CLK_BUFFER") (class "Default")
      (node (ref "IC3") (pin "3") (pinfunction "1Y_3") (pintype "output"))
      (node (ref "R24") (pin "2") (pinfunction "2_2") (pintype "passive"))
    )
    (net (code "62") (name "SYNC_OUT_RUN") (class "Default")
      (node (ref "B1") (pin "D3") (pinfunction "*D3_D3") (pintype "bidirectional"))
      (node (ref "IC2") (pin "12") (pinfunction "4A_12") (pintype "input"))
    )
    (net (code "63") (name "SYNC_OUT_RUN_BUFFER") (class "Default")
      (node (ref "IC2") (pin "11") (pinfunction "4Y_11") (pintype "output"))
      (node (ref "R23") (pin "2") (pinfunction "2_2") (pintype "passive"))
    )
    (net (code "64") (name "TEMPOTAP") (class "Default")
      (node (ref "U$2") (pin "2") (pinfunction "2_2") (pintype "passive"))
      (node (ref "U2") (pin "23") (pinfunction "GPA2_23") (pintype "bidirectional"))
    )
    (net (code "65") (name "unconnected-(B1-*D10-PadD10)") (class "Default")
      (node (ref "B1") (pin "D10") (pinfunction "*D10_D10") (pintype "bidirectional"))
    )
    (net (code "66") (name "unconnected-(B1-*D11-PadD11)") (class "Default")
      (node (ref "B1") (pin "D11") (pinfunction "*D11_D11") (pintype "bidirectional"))
    )
    (net (code "67") (name "unconnected-(B1-Pad5V)") (class "Default")
      (node (ref "B1") (pin "5V") (pinfunction "5V_5V") (pintype "bidirectional"))
    )
    (net (code "68") (name "unconnected-(B1-PadA0)") (class "Default")
      (node (ref "B1") (pin "A0") (pinfunction "A0_A0") (pintype "bidirectional"))
    )
    (net (code "69") (name "unconnected-(B1-PadA1)") (class "Default")
      (node (ref "B1") (pin "A1") (pinfunction "A1_A1") (pintype "bidirectional"))
    )
    (net (code "70") (name "unconnected-(B1-PadA2)") (class "Default")
      (node (ref "B1") (pin "A2") (pinfunction "A2_A2") (pintype "bidirectional"))
    )
    (net (code "71") (name "unconnected-(B1-PadA3)") (class "Default")
      (node (ref "B1") (pin "A3") (pinfunction "A3_A3") (pintype "bidirectional"))
    )
    (net (code "72") (name "unconnected-(B1-PadAREF)") (class "Default")
      (node (ref "B1") (pin "AREF") (pinfunction "AREF_AREF") (pintype "bidirectional"))
    )
    (net (code "73") (name "unconnected-(B1-PadD2)") (class "Default")
      (node (ref "B1") (pin "D2") (pinfunction "D2_D2") (pintype "bidirectional"))
    )
    (net (code "74") (name "unconnected-(B1-PadD12)") (class "Default")
      (node (ref "B1") (pin "D12") (pinfunction "D12_D12") (pintype "bidirectional"))
    )
    (net (code "75") (name "unconnected-(B1-PadD13)") (class "Default")
      (node (ref "B1") (pin "D13") (pinfunction "D13_D13") (pintype "bidirectional"))
    )
    (net (code "76") (name "unconnected-(B1-PadIOREF)") (class "Default")
      (node (ref "B1") (pin "IOREF") (pinfunction "IOREF_IOREF") (pintype "bidirectional"))
    )
    (net (code "77") (name "unconnected-(B1-PadRES)") (class "Default")
      (node (ref "B1") (pin "RES") (pinfunction "RES_RES") (pintype "bidirectional"))
    )
    (net (code "78") (name "unconnected-(B1-PadVIN)") (class "Default")
      (node (ref "B1") (pin "VIN") (pinfunction "VIN_VIN") (pintype "bidirectional"))
    )
    (net (code "79") (name "unconnected-(D11-C-PadK)") (class "Default")
      (node (ref "D11") (pin "K") (pinfunction "C_K") (pintype "passive"))
    )
    (net (code "80") (name "unconnected-(D11-PadA)") (class "Default")
      (node (ref "D11") (pin "A") (pinfunction "A_A") (pintype "passive"))
    )
    (net (code "81") (name "unconnected-(D12-C-PadK)") (class "Default")
      (node (ref "D12") (pin "K") (pinfunction "C_K") (pintype "passive"))
    )
    (net (code "82") (name "unconnected-(D12-PadA)") (class "Default")
      (node (ref "D12") (pin "A") (pinfunction "A_A") (pintype "passive"))
    )
    (net (code "83") (name "unconnected-(D13-C-PadK)") (class "Default")
      (node (ref "D13") (pin "K") (pinfunction "C_K") (pintype "passive"))
    )
    (net (code "84") (name "unconnected-(D13-PadA)") (class "Default")
      (node (ref "D13") (pin "A") (pinfunction "A_A") (pintype "passive"))
    )
    (net (code "85") (name "unconnected-(D14-C-PadK)") (class "Default")
      (node (ref "D14") (pin "K") (pinfunction "C_K") (pintype "passive"))
    )
    (net (code "86") (name "unconnected-(D14-PadA)") (class "Default")
      (node (ref "D14") (pin "A") (pinfunction "A_A") (pintype "passive"))
    )
    (net (code "87") (name "unconnected-(D15-C-PadK)") (class "Default")
      (node (ref "D15") (pin "K") (pinfunction "C_K") (pintype "passive"))
    )
    (net (code "88") (name "unconnected-(D15-PadA)") (class "Default")
      (node (ref "D15") (pin "A") (pinfunction "A_A") (pintype "passive"))
    )
    (net (code "89") (name "unconnected-(D16-C-PadK)") (class "Default")
      (node (ref "D16") (pin "K") (pinfunction "C_K") (pintype "passive"))
    )
    (net (code "90") (name "unconnected-(D16-PadA)") (class "Default")
      (node (ref "D16") (pin "A") (pinfunction "A_A") (pintype "passive"))
    )
    (net (code "91") (name "unconnected-(IC1-VB-Pad7)") (class "Default")
      (node (ref "IC1") (pin "7") (pinfunction "VB_7") (pintype "bidirectional"))
    )
    (net (code "92") (name "unconnected-(IC3-2A-Pad5)") (class "Default")
      (node (ref "IC3") (pin "5") (pinfunction "2A_5") (pintype "input"))
    )
    (net (code "93") (name "unconnected-(IC3-2Y-Pad6)") (class "Default")
      (node (ref "IC3") (pin "6") (pinfunction "2Y_6") (pintype "output"))
    )
    (net (code "94") (name "unconnected-(IC3-3A-Pad9)") (class "Default")
      (node (ref "IC3") (pin "9") (pinfunction "3A_9") (pintype "input"))
    )
    (net (code "95") (name "unconnected-(IC3-3Y-Pad8)") (class "Default")
      (node (ref "IC3") (pin "8") (pinfunction "3Y_8") (pintype "output"))
    )
    (net (code "96") (name "unconnected-(IC3-4A-Pad12)") (class "Default")
      (node (ref "IC3") (pin "12") (pinfunction "4A_12") (pintype "input"))
    )
    (net (code "97") (name "unconnected-(IC3-4Y-Pad11)") (class "Default")
      (node (ref "IC3") (pin "11") (pinfunction "4Y_11") (pintype "output"))
    )
    (net (code "98") (name "unconnected-(IC3-~{3OE}-Pad10)") (class "Default")
      (node (ref "IC3") (pin "10") (pinfunction "~{3OE}_10") (pintype "input"))
    )
    (net (code "99") (name "unconnected-(IC3-~{4OE}-Pad13)") (class "Default")
      (node (ref "IC3") (pin "13") (pinfunction "~{4OE}_13") (pintype "input"))
    )
    (net (code "100") (name "unconnected-(J1-EARTH-Pad1.EARTH)") (class "Default")
      (node (ref "J1") (pin "1.EARTH") (pinfunction "EARTH_1.EARTH") (pintype "bidirectional"))
    )
    (net (code "101") (name "unconnected-(J1-RING-NORM-Pad5.RINGNORM)") (class "Default")
      (node (ref "J1") (pin "5.RINGNORM") (pinfunction "RING-NORM_5.RINGNORM") (pintype "bidirectional"))
    )
    (net (code "102") (name "unconnected-(J1-TIP-NORM-Pad4.TIPNORM)") (class "Default")
      (node (ref "J1") (pin "4.TIPNORM") (pinfunction "TIP-NORM_4.TIPNORM") (pintype "bidirectional"))
    )
    (net (code "103") (name "unconnected-(J2-RING-NORM-Pad5.RINGNORM)") (class "Default")
      (node (ref "J2") (pin "5.RINGNORM") (pinfunction "RING-NORM_5.RINGNORM") (pintype "bidirectional"))
    )
    (net (code "104") (name "unconnected-(J2-TIP-NORM-Pad4.TIPNORM)") (class "Default")
      (node (ref "J2") (pin "4.TIPNORM") (pinfunction "TIP-NORM_4.TIPNORM") (pintype "bidirectional"))
    )
    (net (code "105") (name "unconnected-(J3-TIP-NORM-Pad4.TIPNORM)") (class "Default")
      (node (ref "J3") (pin "4.TIPNORM") (pinfunction "TIP-NORM_4.TIPNORM") (pintype "bidirectional"))
    )
    (net (code "106") (name "unconnected-(J4-TIP-NORM-Pad4.TIPNORM)") (class "Default")
      (node (ref "J4") (pin "4.TIPNORM") (pinfunction "TIP-NORM_4.TIPNORM") (pintype "bidirectional"))
    )
    (net (code "107") (name "unconnected-(J5-TIP-NORM-Pad4.TIPNORM)") (class "Default")
      (node (ref "J5") (pin "4.TIPNORM") (pinfunction "TIP-NORM_4.TIPNORM") (pintype "bidirectional"))
    )
    (net (code "108") (name "unconnected-(J6-EARTH-Pad1.EARTH)") (class "Default")
      (node (ref "J6") (pin "1.EARTH") (pinfunction "EARTH_1.EARTH") (pintype "bidirectional"))
    )
    (net (code "109") (name "unconnected-(J6-RING-NORM-Pad5.RINGNORM)") (class "Default")
      (node (ref "J6") (pin "5.RINGNORM") (pinfunction "RING-NORM_5.RINGNORM") (pintype "bidirectional"))
    )
    (net (code "110") (name "unconnected-(J6-RING-Pad3.RING)") (class "Default")
      (node (ref "J6") (pin "3.RING") (pinfunction "RING_3.RING") (pintype "bidirectional"))
    )
    (net (code "111") (name "unconnected-(J6-TIP-NORM-Pad4.TIPNORM)") (class "Default")
      (node (ref "J6") (pin "4.TIPNORM") (pinfunction "TIP-NORM_4.TIPNORM") (pintype "bidirectional"))
    )
    (net (code "112") (name "unconnected-(J6-TIP-Pad2.TIP)") (class "Default")
      (node (ref "J6") (pin "2.TIP") (pinfunction "TIP_2.TIP") (pintype "bidirectional"))
    )
    (net (code "113") (name "unconnected-(J7-EARTH-Pad1.EARTH)") (class "Default")
      (node (ref "J7") (pin "1.EARTH") (pinfunction "EARTH_1.EARTH") (pintype "bidirectional"))
    )
    (net (code "114") (name "unconnected-(J7-RING-NORM-Pad5.RINGNORM)") (class "Default")
      (node (ref "J7") (pin "5.RINGNORM") (pinfunction "RING-NORM_5.RINGNORM") (pintype "bidirectional"))
    )
    (net (code "115") (name "unconnected-(J7-RING-Pad3.RING)") (class "Default")
      (node (ref "J7") (pin "3.RING") (pinfunction "RING_3.RING") (pintype "bidirectional"))
    )
    (net (code "116") (name "unconnected-(J7-TIP-NORM-Pad4.TIPNORM)") (class "Default")
      (node (ref "J7") (pin "4.TIPNORM") (pinfunction "TIP-NORM_4.TIPNORM") (pintype "bidirectional"))
    )
    (net (code "117") (name "unconnected-(J7-TIP-Pad2.TIP)") (class "Default")
      (node (ref "J7") (pin "2.TIP") (pinfunction "TIP_2.TIP") (pintype "bidirectional"))
    )
    (net (code "118") (name "unconnected-(J8-EARTH-Pad1.EARTH)") (class "Default")
      (node (ref "J8") (pin "1.EARTH") (pinfunction "EARTH_1.EARTH") (pintype "bidirectional"))
    )
    (net (code "119") (name "unconnected-(J8-RING-NORM-Pad5.RINGNORM)") (class "Default")
      (node (ref "J8") (pin "5.RINGNORM") (pinfunction "RING-NORM_5.RINGNORM") (pintype "bidirectional"))
    )
    (net (code "120") (name "unconnected-(J8-RING-Pad3.RING)") (class "Default")
      (node (ref "J8") (pin "3.RING") (pinfunction "RING_3.RING") (pintype "bidirectional"))
    )
    (net (code "121") (name "unconnected-(J8-TIP-NORM-Pad4.TIPNORM)") (class "Default")
      (node (ref "J8") (pin "4.TIPNORM") (pinfunction "TIP-NORM_4.TIPNORM") (pintype "bidirectional"))
    )
    (net (code "122") (name "unconnected-(J8-TIP-Pad2.TIP)") (class "Default")
      (node (ref "J8") (pin "2.TIP") (pinfunction "TIP_2.TIP") (pintype "bidirectional"))
    )
    (net (code "123") (name "unconnected-(J9-EARTH-Pad1.EARTH)") (class "Default")
      (node (ref "J9") (pin "1.EARTH") (pinfunction "EARTH_1.EARTH") (pintype "bidirectional"))
    )
    (net (code "124") (name "unconnected-(J9-RING-NORM-Pad5.RINGNORM)") (class "Default")
      (node (ref "J9") (pin "5.RINGNORM") (pinfunction "RING-NORM_5.RINGNORM") (pintype "bidirectional"))
    )
    (net (code "125") (name "unconnected-(J9-RING-Pad3.RING)") (class "Default")
      (node (ref "J9") (pin "3.RING") (pinfunction "RING_3.RING") (pintype "bidirectional"))
    )
    (net (code "126") (name "unconnected-(J9-TIP-NORM-Pad4.TIPNORM)") (class "Default")
      (node (ref "J9") (pin "4.TIPNORM") (pinfunction "TIP-NORM_4.TIPNORM") (pintype "bidirectional"))
    )
    (net (code "127") (name "unconnected-(J9-TIP-Pad2.TIP)") (class "Default")
      (node (ref "J9") (pin "2.TIP") (pinfunction "TIP_2.TIP") (pintype "bidirectional"))
    )
    (net (code "128") (name "unconnected-(J10-EARTH-Pad1.EARTH)") (class "Default")
      (node (ref "J10") (pin "1.EARTH") (pinfunction "EARTH_1.EARTH") (pintype "bidirectional"))
    )
    (net (code "129") (name "unconnected-(J10-RING-NORM-Pad5.RINGNORM)") (class "Default")
      (node (ref "J10") (pin "5.RINGNORM") (pinfunction "RING-NORM_5.RINGNORM") (pintype "bidirectional"))
    )
    (net (code "130") (name "unconnected-(J10-RING-Pad3.RING)") (class "Default")
      (node (ref "J10") (pin "3.RING") (pinfunction "RING_3.RING") (pintype "bidirectional"))
    )
    (net (code "131") (name "unconnected-(J10-TIP-NORM-Pad4.TIPNORM)") (class "Default")
      (node (ref "J10") (pin "4.TIPNORM") (pinfunction "TIP-NORM_4.TIPNORM") (pintype "bidirectional"))
    )
    (net (code "132") (name "unconnected-(J10-TIP-Pad2.TIP)") (class "Default")
      (node (ref "J10") (pin "2.TIP") (pinfunction "TIP_2.TIP") (pintype "bidirectional"))
    )
    (net (code "133") (name "unconnected-(J11-EARTH-Pad1.EARTH)") (class "Default")
      (node (ref "J11") (pin "1.EARTH") (pinfunction "EARTH_1.EARTH") (pintype "bidirectional"))
    )
    (net (code "134") (name "unconnected-(J11-RING-NORM-Pad5.RINGNORM)") (class "Default")
      (node (ref "J11") (pin "5.RINGNORM") (pinfunction "RING-NORM_5.RINGNORM") (pintype "bidirectional"))
    )
    (net (code "135") (name "unconnected-(J11-RING-Pad3.RING)") (class "Default")
      (node (ref "J11") (pin "3.RING") (pinfunction "RING_3.RING") (pintype "bidirectional"))
    )
    (net (code "136") (name "unconnected-(J11-TIP-NORM-Pad4.TIPNORM)") (class "Default")
      (node (ref "J11") (pin "4.TIPNORM") (pinfunction "TIP-NORM_4.TIPNORM") (pintype "bidirectional"))
    )
    (net (code "137") (name "unconnected-(J11-TIP-Pad2.TIP)") (class "Default")
      (node (ref "J11") (pin "2.TIP") (pinfunction "TIP_2.TIP") (pintype "bidirectional"))
    )
    (net (code "138") (name "unconnected-(J12-EARTH-Pad1.EARTH)") (class "Default")
      (node (ref "J12") (pin "1.EARTH") (pinfunction "EARTH_1.EARTH") (pintype "bidirectional"))
    )
    (net (code "139") (name "unconnected-(J12-RING-NORM-Pad5.RINGNORM)") (class "Default")
      (node (ref "J12") (pin "5.RINGNORM") (pinfunction "RING-NORM_5.RINGNORM") (pintype "bidirectional"))
    )
    (net (code "140") (name "unconnected-(J12-RING-Pad3.RING)") (class "Default")
      (node (ref "J12") (pin "3.RING") (pinfunction "RING_3.RING") (pintype "bidirectional"))
    )
    (net (code "141") (name "unconnected-(J12-TIP-NORM-Pad4.TIPNORM)") (class "Default")
      (node (ref "J12") (pin "4.TIPNORM") (pinfunction "TIP-NORM_4.TIPNORM") (pintype "bidirectional"))
    )
    (net (code "142") (name "unconnected-(J12-TIP-Pad2.TIP)") (class "Default")
      (node (ref "J12") (pin "2.TIP") (pinfunction "TIP_2.TIP") (pintype "bidirectional"))
    )
    (net (code "143") (name "unconnected-(S2-Pad1)") (class "Default")
      (node (ref "S2") (pin "1") (pinfunction "1_1") (pintype "passive"))
    )
    (net (code "144") (name "unconnected-(S2-Pad3)") (class "Default")
      (node (ref "S2") (pin "3") (pinfunction "3_3") (pintype "passive"))
    )
    (net (code "145") (name "unconnected-(S3-Pad1)") (class "Default")
      (node (ref "S3") (pin "1") (pinfunction "1_1") (pintype "passive"))
    )
    (net (code "146") (name "unconnected-(S3-Pad3)") (class "Default")
      (node (ref "S3") (pin "3") (pinfunction "3_3") (pintype "passive"))
    )
    (net (code "147") (name "unconnected-(S7-COM_1-Pad2)") (class "Default")
      (node (ref "S7") (pin "2") (pinfunction "COM_1_2") (pintype "bidirectional"))
    )
    (net (code "148") (name "unconnected-(S7-NC_1-Pad3)") (class "Default")
      (node (ref "S7") (pin "3") (pinfunction "NC_1_3") (pintype "bidirectional"))
    )
    (net (code "149") (name "unconnected-(S7-NC_2-Pad6)") (class "Default")
      (node (ref "S7") (pin "6") (pinfunction "NC_2_6") (pintype "bidirectional"))
    )
    (net (code "150") (name "unconnected-(S7-NO_1-Pad1)") (class "Default")
      (node (ref "S7") (pin "1") (pinfunction "NO_1_1") (pintype "bidirectional"))
    )
    (net (code "151") (name "unconnected-(U1-GPA5-Pad26)") (class "Default")
      (node (ref "U1") (pin "26") (pinfunction "GPA5_26") (pintype "bidirectional"))
    )
    (net (code "152") (name "unconnected-(U1-GPA6-Pad27)") (class "Default")
      (node (ref "U1") (pin "27") (pinfunction "GPA6_27") (pintype "bidirectional"))
    )
    (net (code "153") (name "unconnected-(U1-GPA7-Pad28)") (class "Default")
      (node (ref "U1") (pin "28") (pinfunction "GPA7_28") (pintype "bidirectional"))
    )
    (net (code "154") (name "unconnected-(U1-GPB0-Pad1)") (class "Default")
      (node (ref "U1") (pin "1") (pinfunction "GPB0_1") (pintype "bidirectional"))
    )
    (net (code "155") (name "unconnected-(U1-GPB1-Pad2)") (class "Default")
      (node (ref "U1") (pin "2") (pinfunction "GPB1_2") (pintype "bidirectional"))
    )
    (net (code "156") (name "unconnected-(U1-GPB5-Pad6)") (class "Default")
      (node (ref "U1") (pin "6") (pinfunction "GPB5_6") (pintype "bidirectional"))
    )
    (net (code "157") (name "unconnected-(U1-GPB6-Pad7)") (class "Default")
      (node (ref "U1") (pin "7") (pinfunction "GPB6_7") (pintype "bidirectional"))
    )
    (net (code "158") (name "unconnected-(U1-GPB7-Pad8)") (class "Default")
      (node (ref "U1") (pin "8") (pinfunction "GPB7_8") (pintype "bidirectional"))
    )
    (net (code "159") (name "unconnected-(U1-INTB-Pad19)") (class "Default")
      (node (ref "U1") (pin "19") (pinfunction "INTB_19") (pintype "output"))
    )
    (net (code "160") (name "unconnected-(U2-GPA5-Pad26)") (class "Default")
      (node (ref "U2") (pin "26") (pinfunction "GPA5_26") (pintype "bidirectional"))
    )
    (net (code "161") (name "unconnected-(U2-GPA6-Pad27)") (class "Default")
      (node (ref "U2") (pin "27") (pinfunction "GPA6_27") (pintype "bidirectional"))
    )
    (net (code "162") (name "unconnected-(U2-INTB-Pad19)") (class "Default")
      (node (ref "U2") (pin "19") (pinfunction "INTB_19") (pintype "output"))
    )
    (net (code "163") (name "~{RESET}") (class "Default")
      (node (ref "B1") (pin "D6") (pinfunction "*D6_D6") (pintype "bidirectional"))
      (node (ref "U1") (pin "18") (pinfunction "~{RESET}_18") (pintype "input"))
      (node (ref "U2") (pin "18") (pinfunction "~{RESET}_18") (pintype "input"))
    )
  )
)
